# 2228_Emetteur_Systeme.net
KiCad netlist of a schematic drawn in Altium Designer
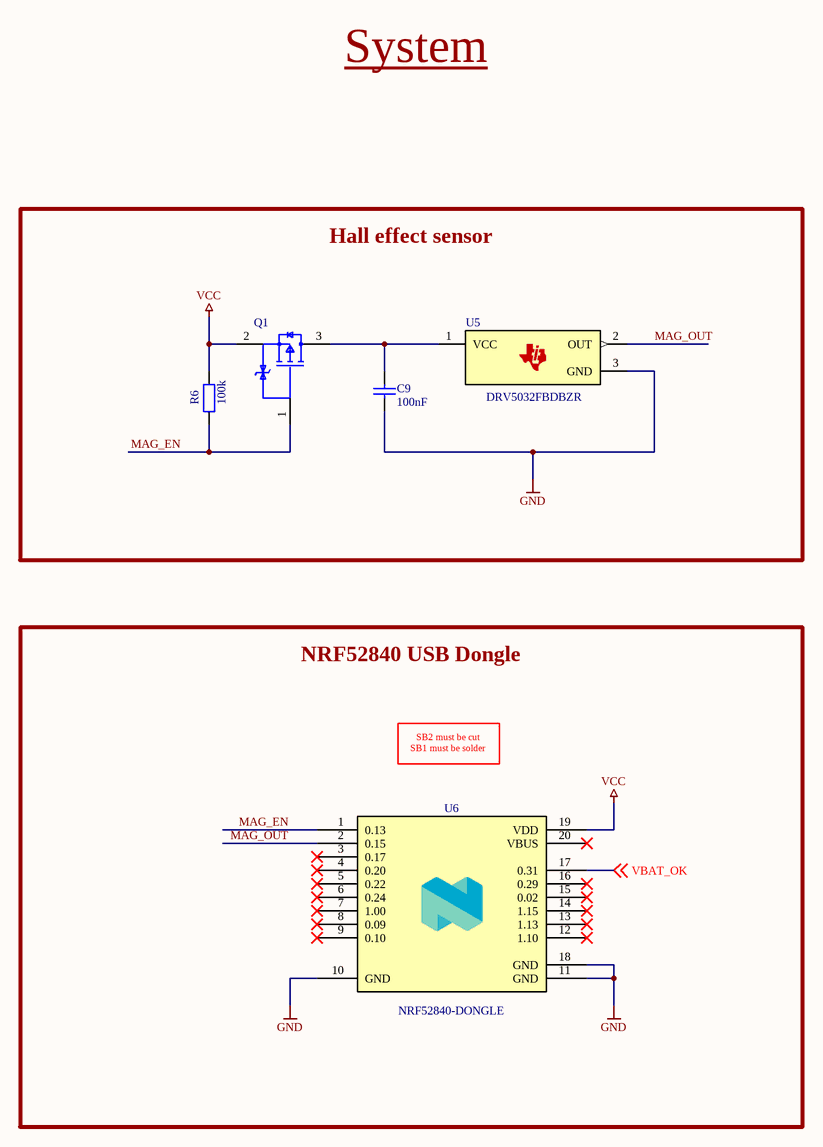
[diagram p0: 2228_Emetteur_Systeme.SchDoc]

(export (version "E")
  (design (tool "Eeschema 10.0.6"))
  (components
    (comp (ref "C9")
      (value "100nF")
      (footprint "CAP_0805")
      (description "Capacitor")
      (fields (field (name "Comment") "CAP_SMD"))
      (libsource (lib "2228_AlarmeFenetre_Symbols") (part "CAP_SMD"))
    )
    (comp (ref "Q1")
      (value "RZM001P02T2L")
      (footprint "FP-VMT3-MFG")
      (description "MOSFET P-CH 20V 0.1A VMT3")
      (fields
        (field (name "OCTOPART") "https://octopart.com/rzm001p02t2l-rohm-29677415")
        (field (name "MANUFACTURER") "Rohm")
      )
      (libsource (lib "Altium Content Vault") (part "2b2cac828553558a1ef0da1d67e22de"))
    )
    (comp (ref "R6")
      (value "100k")
      (footprint "RES_0805")
      (fields (field (name "Comment") "RES_SMD"))
      (libsource (lib "2228_AlarmeFenetre_Symbols") (part "RES_SMD"))
    )
    (comp (ref "U5")
      (value "DRV5032FBDBZR")
      (footprint "2228_AlarmeFenetre_Footprints:SOT95P237X112-3N")
      (fields (field (name "MANUFACTURER") "Texas Instruments"))
      (libsource (lib "2228_AlarmeFenetre_Symbols") (part "DRV5032FBDBZR"))
    )
    (comp (ref "U6")
      (value "NRF52840-DONGLE")
      (footprint "NRF52840_DONGLE")
      (fields (field (name "MANUFACTURER") "Nordic Semiconductor"))
      (libsource (lib "2228_AlarmeFenetre_Symbols") (part "NRF52840-DONGLE"))
    )
  )
  (nets
    (net (code "1") (name "/MAG_EN") (class "Default")
      (node (ref "Q1") (pin "1") (pinfunction "Gate_1") (pintype "passive"))
      (node (ref "R6") (pin "1") (pinfunction "1_1") (pintype "passive"))
      (node (ref "U6") (pin "1") (pinfunction "0.13_1") (pintype "passive"))
    )
    (net (code "2") (name "/MAG_OUT") (class "Default")
      (node (ref "U5") (pin "2") (pinfunction "OUT_2") (pintype "output"))
      (node (ref "U6") (pin "2") (pinfunction "0.15_2") (pintype "passive"))
    )
    (net (code "3") (name "GND") (class "Default")
      (node (ref "C9") (pin "1") (pinfunction "1_1") (pintype "passive"))
      (node (ref "U5") (pin "3") (pinfunction "GND_3") (pintype "power_in"))
      (node (ref "U6") (pin "10") (pinfunction "GND_10") (pintype "passive"))
      (node (ref "U6") (pin "11") (pinfunction "GND_11") (pintype "passive"))
      (node (ref "U6") (pin "18") (pinfunction "GND_18") (pintype "passive"))
    )
    (net (code "4") (name "Net-(Q1-Drain)") (class "Default")
      (node (ref "C9") (pin "2") (pinfunction "2_2") (pintype "passive"))
      (node (ref "Q1") (pin "3") (pinfunction "Drain_3") (pintype "passive"))
      (node (ref "U5") (pin "1") (pinfunction "VCC_1") (pintype "power_in"))
    )
    (net (code "5") (name "VBAT_OK") (class "Default")
      (node (ref "U6") (pin "17") (pinfunction "0.31_17") (pintype "passive"))
    )
    (net (code "6") (name "VCC") (class "Default")
      (node (ref "Q1") (pin "2") (pinfunction "Source_2") (pintype "passive"))
      (node (ref "R6") (pin "2") (pinfunction "2_2") (pintype "passive"))
      (node (ref "U6") (pin "19") (pinfunction "VDD_19") (pintype "passive"))
    )
    (net (code "7") (name "unconnected-(U6-0.02-Pad15)") (class "Default")
      (node (ref "U6") (pin "15") (pinfunction "0.02_15") (pintype "passive+no_connect"))
    )
    (net (code "8") (name "unconnected-(U6-0.09-Pad8)") (class "Default")
      (node (ref "U6") (pin "8") (pinfunction "0.09_8") (pintype "passive+no_connect"))
    )
    (net (code "9") (name "unconnected-(U6-0.10-Pad9)") (class "Default")
      (node (ref "U6") (pin "9") (pinfunction "0.10_9") (pintype "passive+no_connect"))
    )
    (net (code "10") (name "unconnected-(U6-0.17-Pad3)") (class "Default")
      (node (ref "U6") (pin "3") (pinfunction "0.17_3") (pintype "passive+no_connect"))
    )
    (net (code "11") (name "unconnected-(U6-0.20-Pad4)") (class "Default")
      (node (ref "U6") (pin "4") (pinfunction "0.20_4") (pintype "passive+no_connect"))
    )
    (net (code "12") (name "unconnected-(U6-0.22-Pad5)") (class "Default")
      (node (ref "U6") (pin "5") (pinfunction "0.22_5") (pintype "passive+no_connect"))
    )
    (net (code "13") (name "unconnected-(U6-0.24-Pad6)") (class "Default")
      (node (ref "U6") (pin "6") (pinfunction "0.24_6") (pintype "passive+no_connect"))
    )
    (net (code "14") (name "unconnected-(U6-0.29-Pad16)") (class "Default")
      (node (ref "U6") (pin "16") (pinfunction "0.29_16") (pintype "passive+no_connect"))
    )
    (net (code "15") (name "unconnected-(U6-1.00-Pad7)") (class "Default")
      (node (ref "U6") (pin "7") (pinfunction "1.00_7") (pintype "passive+no_connect"))
    )
    (net (code "16") (name "unconnected-(U6-1.10-Pad12)") (class "Default")
      (node (ref "U6") (pin "12") (pinfunction "1.10_12") (pintype "passive+no_connect"))
    )
    (net (code "17") (name "unconnected-(U6-1.13-Pad13)") (class "Default")
      (node (ref "U6") (pin "13") (pinfunction "1.13_13") (pintype "passive+no_connect"))
    )
    (net (code "18") (name "unconnected-(U6-1.15-Pad14)") (class "Default")
      (node (ref "U6") (pin "14") (pinfunction "1.15_14") (pintype "passive+no_connect"))
    )
    (net (code "19") (name "unconnected-(U6-VBUS-Pad20)") (class "Default")
      (node (ref "U6") (pin "20") (pinfunction "VBUS_20") (pintype "passive+no_connect"))
    )
  )
)
